# lt308x_test_board-v0001.net
KiCad netlist of a schematic drawn in EAGLE
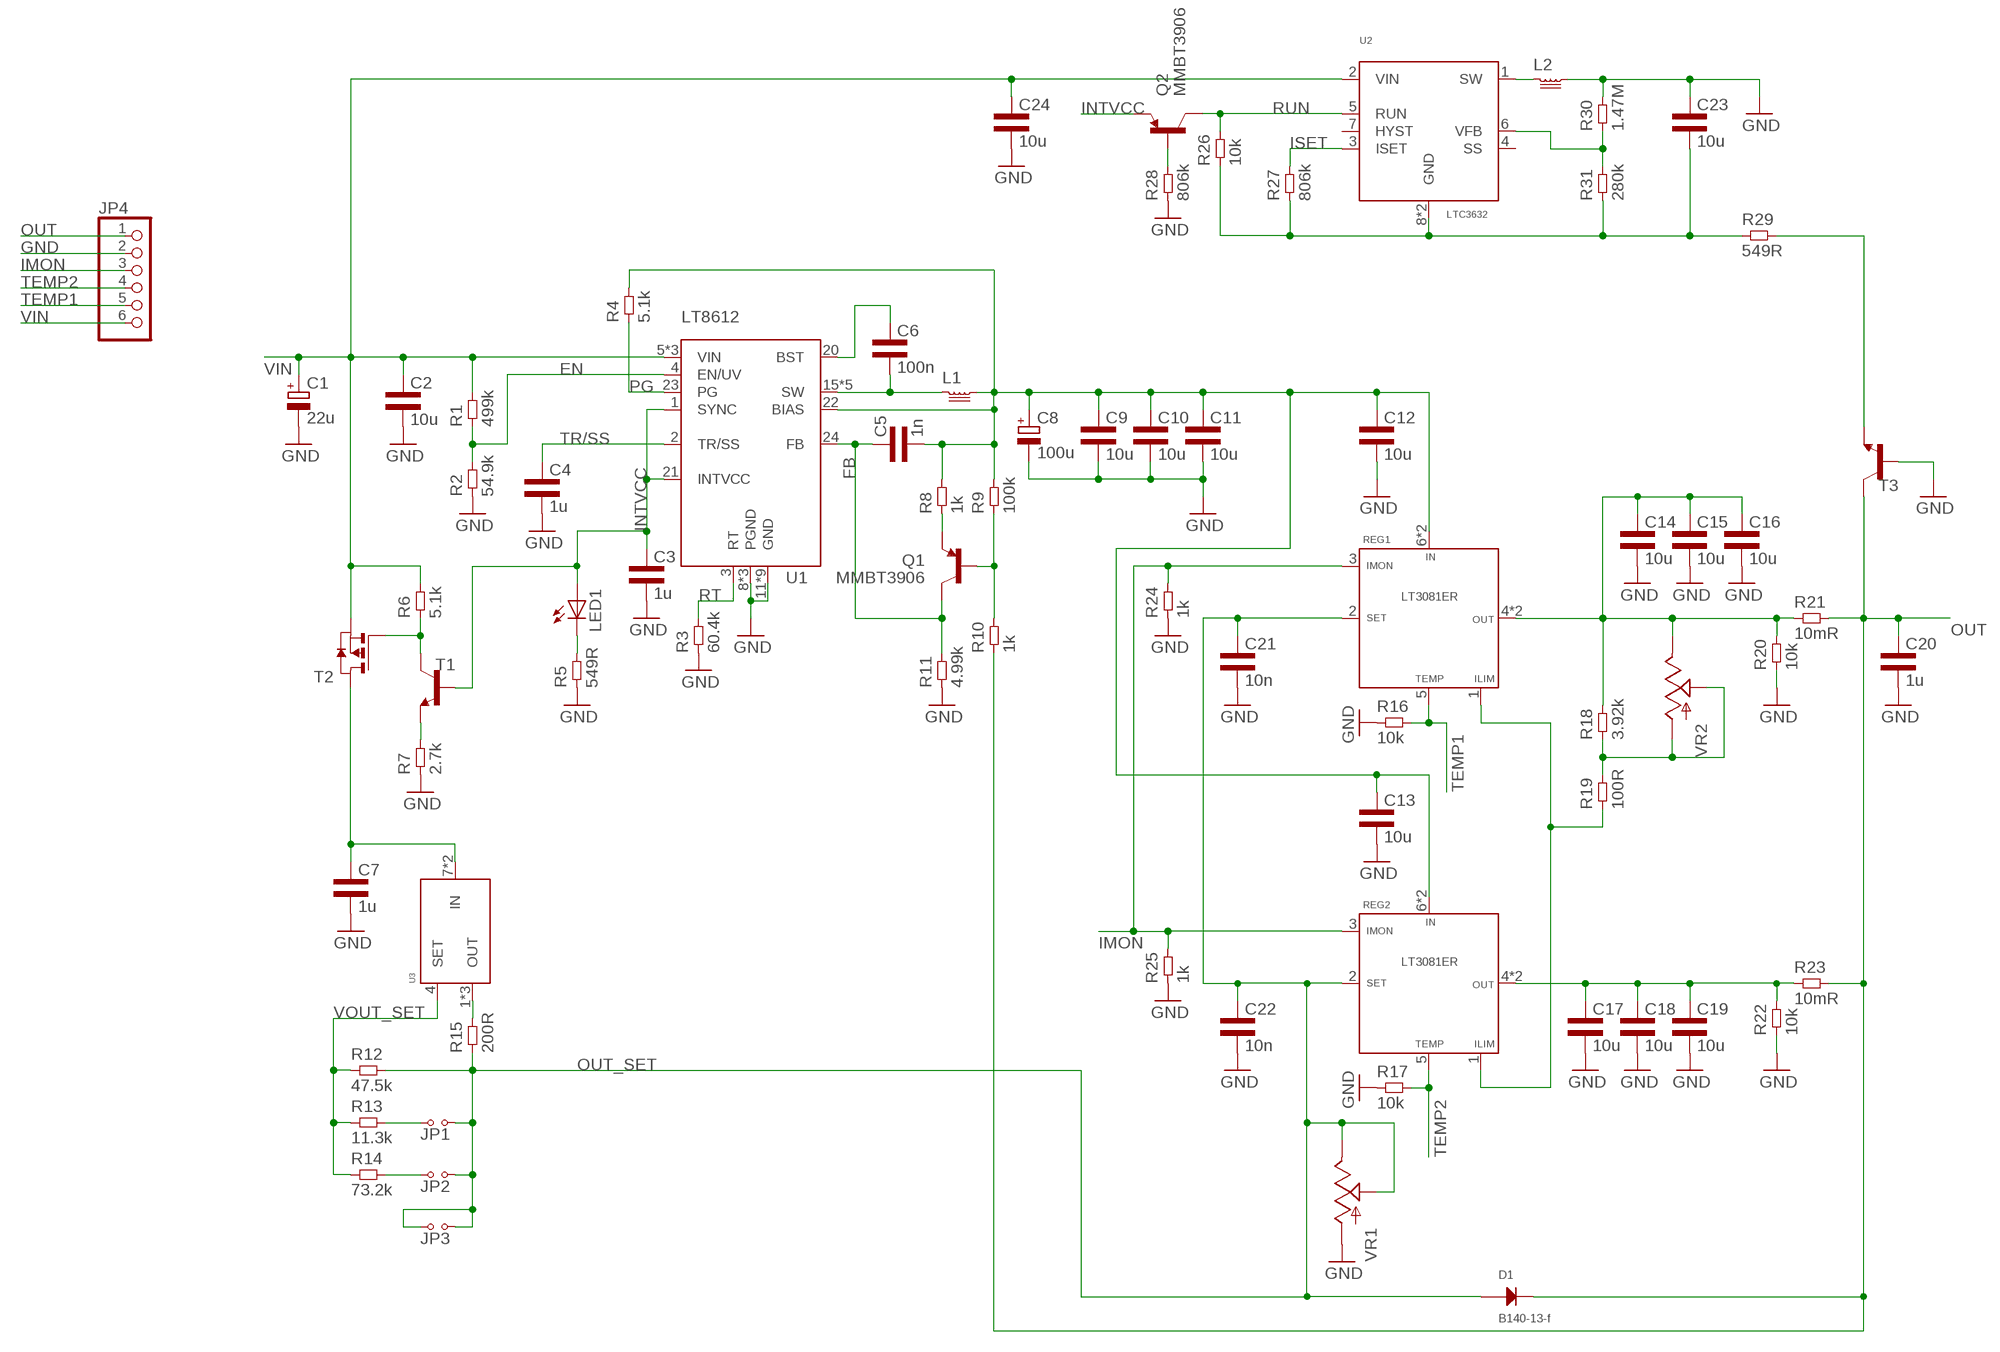
[diagram p0: schematic, sheet 1]

(export (version "E")
  (design (tool "Eeschema 10.0.6"))
  (components
    (comp (ref "C1")
      (value "22u")
      (footprint "eagle-import:UD-6,3X7,7_NICHICON")
      (libsource (lib "eagle-import") (part "CPOL-EUUD-6,3X7,7"))
    )
    (comp (ref "C2")
      (value "10u")
      (footprint "eagle-import:1210L3")
      (libsource (lib "eagle-import") (part "CAP1210L3"))
    )
    (comp (ref "C3")
      (value "1u")
      (footprint "eagle-import:0603L3")
      (libsource (lib "eagle-import") (part "CAP0603L3"))
    )
    (comp (ref "C4")
      (value "1u")
      (footprint "eagle-import:0603L3")
      (libsource (lib "eagle-import") (part "CAP0603L3"))
    )
    (comp (ref "C5")
      (value "1n")
      (footprint "eagle-import:0603L3")
      (libsource (lib "eagle-import") (part "CAP0603L3"))
    )
    (comp (ref "C6")
      (value "100n")
      (footprint "eagle-import:0603L3")
      (libsource (lib "eagle-import") (part "CAP0603L3"))
    )
    (comp (ref "C7")
      (value "1u")
      (footprint "eagle-import:0805L3")
      (libsource (lib "eagle-import") (part "CAP0805L3"))
    )
    (comp (ref "C8")
      (value "100u")
      (footprint "eagle-import:UD-6,3X7,7_NICHICON")
      (libsource (lib "eagle-import") (part "CPOL-EUUD-6,3X7,7"))
    )
    (comp (ref "C9")
      (value "10u")
      (footprint "eagle-import:1210L3")
      (libsource (lib "eagle-import") (part "CAP1210L3"))
    )
    (comp (ref "C10")
      (value "10u")
      (footprint "eagle-import:1210L3")
      (libsource (lib "eagle-import") (part "CAP1210L3"))
    )
    (comp (ref "C11")
      (value "10u")
      (footprint "eagle-import:1210L3")
      (libsource (lib "eagle-import") (part "CAP1210L3"))
    )
    (comp (ref "C12")
      (value "10u")
      (footprint "eagle-import:1210L3")
      (libsource (lib "eagle-import") (part "CAP1210L3"))
    )
    (comp (ref "C13")
      (value "10u")
      (footprint "eagle-import:1210L3")
      (libsource (lib "eagle-import") (part "CAP1210L3"))
    )
    (comp (ref "C14")
      (value "10u")
      (footprint "eagle-import:1210L3")
      (libsource (lib "eagle-import") (part "CAP1210L3"))
    )
    (comp (ref "C15")
      (value "10u")
      (footprint "eagle-import:1210L3")
      (libsource (lib "eagle-import") (part "CAP1210L3"))
    )
    (comp (ref "C16")
      (value "10u")
      (footprint "eagle-import:1210L3")
      (libsource (lib "eagle-import") (part "CAP1210L3"))
    )
    (comp (ref "C17")
      (value "10u")
      (footprint "eagle-import:1210L3")
      (libsource (lib "eagle-import") (part "CAP1210L3"))
    )
    (comp (ref "C18")
      (value "10u")
      (footprint "eagle-import:1210L3")
      (libsource (lib "eagle-import") (part "CAP1210L3"))
    )
    (comp (ref "C19")
      (value "10u")
      (footprint "eagle-import:1210L3")
      (libsource (lib "eagle-import") (part "CAP1210L3"))
    )
    (comp (ref "C20")
      (value "1u")
      (footprint "eagle-import:1206L3")
      (libsource (lib "eagle-import") (part "CAP1206L3"))
    )
    (comp (ref "C21")
      (value "10n")
      (footprint "eagle-import:0603L3")
      (libsource (lib "eagle-import") (part "CAP0603L3"))
    )
    (comp (ref "C22")
      (value "10n")
      (footprint "eagle-import:0603L3")
      (libsource (lib "eagle-import") (part "CAP0603L3"))
    )
    (comp (ref "C23")
      (value "10u")
      (footprint "eagle-import:0805L3")
      (libsource (lib "eagle-import") (part "CAP0805L3"))
    )
    (comp (ref "C24")
      (value "10u")
      (footprint "eagle-import:0805L3")
      (libsource (lib "eagle-import") (part "CAP0805L3"))
    )
    (comp (ref "D1")
      (value "B140-13-f")
      (footprint "eagle-import:SMA-2")
      (libsource (lib "eagle-import") (part "DIODESMA"))
    )
    (comp (ref "JP1")
      (value "JUMPER2")
      (footprint "eagle-import:JUMPER2")
      (libsource (lib "eagle-import") (part "JUMPER2"))
    )
    (comp (ref "JP2")
      (value "JUMPER2")
      (footprint "eagle-import:JUMPER2")
      (libsource (lib "eagle-import") (part "JUMPER2"))
    )
    (comp (ref "JP3")
      (value "JUMPER2")
      (footprint "eagle-import:JUMPER2")
      (libsource (lib "eagle-import") (part "JUMPER2"))
    )
    (comp (ref "JP4")
      (value "PINHD-1X6")
      (footprint "eagle-import:1X06")
      (libsource (lib "eagle-import") (part "PINHD-1X6"))
    )
    (comp (ref "L1")
      (value "INDUCTOR10.5X10.5")
      (footprint "eagle-import:10.5X10.5")
      (libsource (lib "eagle-import") (part "INDUCTOR10.5X10.5"))
    )
    (comp (ref "L2")
      (value "INDUCTOR1210L1")
      (footprint "eagle-import:1210L1")
      (libsource (lib "eagle-import") (part "INDUCTOR1210L1"))
    )
    (comp (ref "LED1")
      (value "LEDCHIPLED_0805")
      (footprint "eagle-import:CHIPLED_0805")
      (libsource (lib "eagle-import") (part "LEDCHIPLED_0805"))
    )
    (comp (ref "Q1")
      (value "MMBT3906")
      (footprint "eagle-import:SOT23")
      (libsource (lib "eagle-import") (part "TRANSISTOR_PNPMMBT3906"))
    )
    (comp (ref "Q2")
      (value "MMBT3906")
      (footprint "eagle-import:SOT23")
      (libsource (lib "eagle-import") (part "TRANSISTOR_PNPMMBT3906"))
    )
    (comp (ref "R1")
      (value "499k")
      (footprint "eagle-import:0603L3")
      (libsource (lib "eagle-import") (part "RES0603L3"))
    )
    (comp (ref "R2")
      (value "54.9k")
      (footprint "eagle-import:0603L3")
      (libsource (lib "eagle-import") (part "RES0603L3"))
    )
    (comp (ref "R3")
      (value "60.4k")
      (footprint "eagle-import:0603L3")
      (libsource (lib "eagle-import") (part "RES0603L3"))
    )
    (comp (ref "R4")
      (value "5.1k")
      (footprint "eagle-import:0603L3")
      (libsource (lib "eagle-import") (part "RES0603L3"))
    )
    (comp (ref "R5")
      (value "549R")
      (footprint "eagle-import:0603L3")
      (libsource (lib "eagle-import") (part "RES0603L3"))
    )
    (comp (ref "R6")
      (value "5.1k")
      (footprint "eagle-import:0603L3")
      (libsource (lib "eagle-import") (part "RES0603L3"))
    )
    (comp (ref "R7")
      (value "2.7k")
      (footprint "eagle-import:0603L3")
      (libsource (lib "eagle-import") (part "RES0603L3"))
    )
    (comp (ref "R8")
      (value "1k")
      (footprint "eagle-import:0603L3")
      (libsource (lib "eagle-import") (part "RES0603L3"))
    )
    (comp (ref "R9")
      (value "100k")
      (footprint "eagle-import:0603L3")
      (libsource (lib "eagle-import") (part "RES0603L3"))
    )
    (comp (ref "R10")
      (value "1k")
      (footprint "eagle-import:0603L3")
      (libsource (lib "eagle-import") (part "RES0603L3"))
    )
    (comp (ref "R11")
      (value "4.99k")
      (footprint "eagle-import:0603L3")
      (libsource (lib "eagle-import") (part "RES0603L3"))
    )
    (comp (ref "R12")
      (value "47.5k")
      (footprint "eagle-import:0603L3")
      (libsource (lib "eagle-import") (part "RES0603L3"))
    )
    (comp (ref "R13")
      (value "11.3k")
      (footprint "eagle-import:0603L3")
      (libsource (lib "eagle-import") (part "RES0603L3"))
    )
    (comp (ref "R14")
      (value "73.2k")
      (footprint "eagle-import:0603L3")
      (libsource (lib "eagle-import") (part "RES0603L3"))
    )
    (comp (ref "R15")
      (value "200R")
      (footprint "eagle-import:0805L3")
      (libsource (lib "eagle-import") (part "RES0805L3"))
    )
    (comp (ref "R16")
      (value "10k")
      (footprint "eagle-import:0603L3")
      (libsource (lib "eagle-import") (part "RES0603L3"))
    )
    (comp (ref "R17")
      (value "10k")
      (footprint "eagle-import:0603L3")
      (libsource (lib "eagle-import") (part "RES0603L3"))
    )
    (comp (ref "R18")
      (value "3.92k")
      (footprint "eagle-import:0603L3")
      (libsource (lib "eagle-import") (part "RES0603L3"))
    )
    (comp (ref "R19")
      (value "100R")
      (footprint "eagle-import:0603L3")
      (libsource (lib "eagle-import") (part "RES0603L3"))
    )
    (comp (ref "R20")
      (value "10k")
      (footprint "eagle-import:1210L3")
      (libsource (lib "eagle-import") (part "RES1210L3"))
    )
    (comp (ref "R21")
      (value "10mR")
      (footprint "eagle-import:1210L3")
      (libsource (lib "eagle-import") (part "RES1210L3"))
    )
    (comp (ref "R22")
      (value "10k")
      (footprint "eagle-import:1210L3")
      (libsource (lib "eagle-import") (part "RES1210L3"))
    )
    (comp (ref "R23")
      (value "10mR")
      (footprint "eagle-import:1210L3")
      (libsource (lib "eagle-import") (part "RES1210L3"))
    )
    (comp (ref "R24")
      (value "1k")
      (footprint "eagle-import:0603L3")
      (libsource (lib "eagle-import") (part "RES0603L3"))
    )
    (comp (ref "R25")
      (value "1k")
      (footprint "eagle-import:0603L3")
      (libsource (lib "eagle-import") (part "RES0603L3"))
    )
    (comp (ref "R26")
      (value "10k")
      (footprint "eagle-import:0603L3")
      (libsource (lib "eagle-import") (part "RES0603L3"))
    )
    (comp (ref "R27")
      (value "806k")
      (footprint "eagle-import:0603L3")
      (libsource (lib "eagle-import") (part "RES0603L3"))
    )
    (comp (ref "R28")
      (value "806k")
      (footprint "eagle-import:0603L3")
      (libsource (lib "eagle-import") (part "RES0603L3"))
    )
    (comp (ref "R29")
      (value "549R")
      (footprint "eagle-import:0603L3")
      (libsource (lib "eagle-import") (part "RES0603L3"))
    )
    (comp (ref "R30")
      (value "1.47M")
      (footprint "eagle-import:0603L3")
      (libsource (lib "eagle-import") (part "RES0603L3"))
    )
    (comp (ref "R31")
      (value "280k")
      (footprint "eagle-import:0603L3")
      (libsource (lib "eagle-import") (part "RES0603L3"))
    )
    (comp (ref "REG1")
      (value "LT3081ER")
      (footprint "eagle-import:DPAK-7")
      (libsource (lib "eagle-import") (part "LT3081ER"))
    )
    (comp (ref "REG2")
      (value "LT3081ER")
      (footprint "eagle-import:DPAK-7")
      (libsource (lib "eagle-import") (part "LT3081ER"))
    )
    (comp (ref "T1")
      (value "TRANSISTOR_MMBT3904LT1-NPN-SOT23-BEC")
      (footprint "eagle-import:TRANSISTOR_SOT23-BEC")
      (libsource (lib "eagle-import") (part "TRANSISTOR_-NPN-SOT23-BECMMBT3904LT1"))
    )
    (comp (ref "T2")
      (value "PMOSSOT23")
      (footprint "eagle-import:SOT-23")
      (libsource (lib "eagle-import") (part "PMOSSOT23"))
    )
    (comp (ref "T3")
      (value "TRANSISTOR_MMBT3904LT1-NPN-SOT23-BEC")
      (footprint "eagle-import:TRANSISTOR_SOT23-BEC")
      (libsource (lib "eagle-import") (part "TRANSISTOR_-NPN-SOT23-BECMMBT3904LT1"))
    )
    (comp (ref "U1")
      (value "LT8612")
      (footprint "eagle-import:UDE-3X6")
      (libsource (lib "eagle-import") (part "LT8612"))
    )
    (comp (ref "U2")
      (value "LTC3632")
      (footprint "eagle-import:DFN-3X3")
      (libsource (lib "eagle-import") (part "LTC3632"))
    )
    (comp (ref "U3")
      (value "LT3092")
      (footprint "eagle-import:DD-8")
      (libsource (lib "eagle-import") (part "LT3092"))
    )
    (comp (ref "VR1")
      (value "POT")
      (footprint "eagle-import:ALPS_POT")
      (libsource (lib "eagle-import") (part "POT"))
    )
    (comp (ref "VR2")
      (value "POT")
      (footprint "eagle-import:ALPS_POT")
      (libsource (lib "eagle-import") (part "POT"))
    )
  )
  (nets
    (net (code "1") (name "/EN") (class "Default")
      (node (ref "R1") (pin "P$1") (pinfunction "1_P$1") (pintype "bidirectional"))
      (node (ref "R2") (pin "P$2") (pinfunction "2_P$2") (pintype "bidirectional"))
      (node (ref "U1") (pin "4") (pinfunction "EN/UV_4") (pintype "bidirectional"))
    )
    (net (code "2") (name "/FB") (class "Default")
      (node (ref "C5") (pin "P$1") (pinfunction "1_P$1") (pintype "bidirectional"))
      (node (ref "Q1") (pin "3") (pinfunction "C_3") (pintype "passive"))
      (node (ref "R11") (pin "P$2") (pinfunction "2_P$2") (pintype "bidirectional"))
      (node (ref "U1") (pin "24") (pinfunction "FB_24") (pintype "bidirectional"))
    )
    (net (code "3") (name "/IMON") (class "Default")
      (node (ref "JP4") (pin "3") (pinfunction "3_3") (pintype "passive"))
      (node (ref "R24") (pin "P$2") (pinfunction "2_P$2") (pintype "bidirectional"))
      (node (ref "R25") (pin "P$2") (pinfunction "2_P$2") (pintype "bidirectional"))
      (node (ref "REG1") (pin "3") (pinfunction "IMON_3") (pintype "bidirectional"))
      (node (ref "REG2") (pin "3") (pinfunction "IMON_3") (pintype "bidirectional"))
    )
    (net (code "4") (name "/INTVCC") (class "Default")
      (node (ref "C3") (pin "P$1") (pinfunction "1_P$1") (pintype "bidirectional"))
      (node (ref "LED1") (pin "A") (pinfunction "A_A") (pintype "passive"))
      (node (ref "Q2") (pin "2") (pinfunction "E_2") (pintype "passive"))
      (node (ref "T1") (pin "B") (pinfunction "B_B") (pintype "passive"))
      (node (ref "U1") (pin "1") (pinfunction "SYNC_1") (pintype "bidirectional"))
      (node (ref "U1") (pin "21") (pinfunction "INTVCC_21") (pintype "bidirectional"))
    )
    (net (code "5") (name "/ISET") (class "Default")
      (node (ref "R27") (pin "P$2") (pinfunction "2_P$2") (pintype "bidirectional"))
      (node (ref "U2") (pin "3") (pinfunction "ISET_3") (pintype "bidirectional"))
    )
    (net (code "6") (name "/OUT") (class "Default")
      (node (ref "C20") (pin "1") (pinfunction "1_1") (pintype "bidirectional"))
      (node (ref "D1") (pin "2") (pinfunction "CATHODE_2") (pintype "bidirectional"))
      (node (ref "JP4") (pin "1") (pinfunction "1_1") (pintype "passive"))
      (node (ref "R10") (pin "P$1") (pinfunction "1_P$1") (pintype "bidirectional"))
      (node (ref "R21") (pin "P$2") (pinfunction "2_P$2") (pintype "bidirectional"))
      (node (ref "R23") (pin "P$2") (pinfunction "2_P$2") (pintype "bidirectional"))
      (node (ref "T3") (pin "C") (pinfunction "C_C") (pintype "passive"))
    )
    (net (code "7") (name "/OUT_SET") (class "Default")
      (node (ref "C21") (pin "P$1") (pinfunction "1_P$1") (pintype "bidirectional"))
      (node (ref "C22") (pin "P$1") (pinfunction "1_P$1") (pintype "bidirectional"))
      (node (ref "D1") (pin "1") (pinfunction "ANODE_1") (pintype "bidirectional"))
      (node (ref "JP1") (pin "2") (pinfunction "2_2") (pintype "bidirectional"))
      (node (ref "JP2") (pin "2") (pinfunction "2_2") (pintype "bidirectional"))
      (node (ref "JP3") (pin "1") (pinfunction "1_1") (pintype "bidirectional"))
      (node (ref "JP3") (pin "2") (pinfunction "2_2") (pintype "bidirectional"))
      (node (ref "R12") (pin "P$2") (pinfunction "2_P$2") (pintype "bidirectional"))
      (node (ref "R15") (pin "1") (pinfunction "1_1") (pintype "bidirectional"))
      (node (ref "REG1") (pin "2") (pinfunction "SET_2") (pintype "bidirectional"))
      (node (ref "REG2") (pin "2") (pinfunction "SET_2") (pintype "bidirectional"))
      (node (ref "VR1") (pin "P$1") (pinfunction "E_P$1") (pintype "passive"))
      (node (ref "VR1") (pin "P$2") (pinfunction "S_P$2") (pintype "passive"))
    )
    (net (code "8") (name "/PG") (class "Default")
      (node (ref "R4") (pin "P$1") (pinfunction "1_P$1") (pintype "bidirectional"))
      (node (ref "U1") (pin "23") (pinfunction "PG_23") (pintype "bidirectional"))
    )
    (net (code "9") (name "/RT") (class "Default")
      (node (ref "R3") (pin "P$2") (pinfunction "2_P$2") (pintype "bidirectional"))
      (node (ref "U1") (pin "3") (pinfunction "RT_3") (pintype "bidirectional"))
    )
    (net (code "10") (name "/RUN") (class "Default")
      (node (ref "Q2") (pin "3") (pinfunction "C_3") (pintype "passive"))
      (node (ref "R26") (pin "P$2") (pinfunction "2_P$2") (pintype "bidirectional"))
      (node (ref "U2") (pin "5") (pinfunction "RUN_5") (pintype "bidirectional"))
    )
    (net (code "11") (name "/TEMP1") (class "Default")
      (node (ref "JP4") (pin "5") (pinfunction "5_5") (pintype "passive"))
      (node (ref "R16") (pin "P$2") (pinfunction "2_P$2") (pintype "bidirectional"))
      (node (ref "REG1") (pin "5") (pinfunction "TEMP_5") (pintype "bidirectional"))
    )
    (net (code "12") (name "/TEMP2") (class "Default")
      (node (ref "JP4") (pin "4") (pinfunction "4_4") (pintype "passive"))
      (node (ref "R17") (pin "P$2") (pinfunction "2_P$2") (pintype "bidirectional"))
      (node (ref "REG2") (pin "5") (pinfunction "TEMP_5") (pintype "bidirectional"))
    )
    (net (code "13") (name "/TR{slash}SS") (class "Default")
      (node (ref "C4") (pin "P$1") (pinfunction "1_P$1") (pintype "bidirectional"))
      (node (ref "U1") (pin "2") (pinfunction "TR/SS_2") (pintype "bidirectional"))
    )
    (net (code "14") (name "/VIN") (class "Default")
      (node (ref "C1") (pin "+") (pinfunction "+_+") (pintype "passive"))
      (node (ref "C2") (pin "P$1") (pinfunction "1_P$1") (pintype "bidirectional"))
      (node (ref "C24") (pin "1") (pinfunction "1_1") (pintype "bidirectional"))
      (node (ref "JP4") (pin "6") (pinfunction "6_6") (pintype "passive"))
      (node (ref "R1") (pin "P$2") (pinfunction "2_P$2") (pintype "bidirectional"))
      (node (ref "R6") (pin "P$2") (pinfunction "2_P$2") (pintype "bidirectional"))
      (node (ref "T2") (pin "2") (pinfunction "S_2") (pintype "passive"))
      (node (ref "U1") (pin "5") (pinfunction "VIN_5") (pintype "bidirectional"))
      (node (ref "U1") (pin "6") (pinfunction "VIN_6") (pintype "bidirectional"))
      (node (ref "U1") (pin "7") (pinfunction "VIN_7") (pintype "bidirectional"))
      (node (ref "U2") (pin "2") (pinfunction "VIN_2") (pintype "bidirectional"))
    )
    (net (code "15") (name "/VOUT_SET") (class "Default")
      (node (ref "R12") (pin "P$1") (pinfunction "1_P$1") (pintype "bidirectional"))
      (node (ref "R13") (pin "P$1") (pinfunction "1_P$1") (pintype "bidirectional"))
      (node (ref "R14") (pin "P$1") (pinfunction "1_P$1") (pintype "bidirectional"))
      (node (ref "U3") (pin "4") (pinfunction "SET_4") (pintype "bidirectional"))
    )
    (net (code "16") (name "GND") (class "Default")
      (node (ref "C1") (pin "-") (pinfunction "-_-") (pintype "passive"))
      (node (ref "C10") (pin "P$2") (pinfunction "2_P$2") (pintype "bidirectional"))
      (node (ref "C11") (pin "P$2") (pinfunction "2_P$2") (pintype "bidirectional"))
      (node (ref "C12") (pin "P$2") (pinfunction "2_P$2") (pintype "bidirectional"))
      (node (ref "C13") (pin "P$2") (pinfunction "2_P$2") (pintype "bidirectional"))
      (node (ref "C14") (pin "P$2") (pinfunction "2_P$2") (pintype "bidirectional"))
      (node (ref "C15") (pin "P$2") (pinfunction "2_P$2") (pintype "bidirectional"))
      (node (ref "C16") (pin "P$2") (pinfunction "2_P$2") (pintype "bidirectional"))
      (node (ref "C17") (pin "P$2") (pinfunction "2_P$2") (pintype "bidirectional"))
      (node (ref "C18") (pin "P$2") (pinfunction "2_P$2") (pintype "bidirectional"))
      (node (ref "C19") (pin "P$2") (pinfunction "2_P$2") (pintype "bidirectional"))
      (node (ref "C2") (pin "P$2") (pinfunction "2_P$2") (pintype "bidirectional"))
      (node (ref "C20") (pin "2") (pinfunction "2_2") (pintype "bidirectional"))
      (node (ref "C21") (pin "P$2") (pinfunction "2_P$2") (pintype "bidirectional"))
      (node (ref "C22") (pin "P$2") (pinfunction "2_P$2") (pintype "bidirectional"))
      (node (ref "C23") (pin "1") (pinfunction "1_1") (pintype "bidirectional"))
      (node (ref "C24") (pin "2") (pinfunction "2_2") (pintype "bidirectional"))
      (node (ref "C3") (pin "P$2") (pinfunction "2_P$2") (pintype "bidirectional"))
      (node (ref "C4") (pin "P$2") (pinfunction "2_P$2") (pintype "bidirectional"))
      (node (ref "C7") (pin "2") (pinfunction "2_2") (pintype "bidirectional"))
      (node (ref "C8") (pin "-") (pinfunction "-_-") (pintype "passive"))
      (node (ref "C9") (pin "P$2") (pinfunction "2_P$2") (pintype "bidirectional"))
      (node (ref "JP4") (pin "2") (pinfunction "2_2") (pintype "passive"))
      (node (ref "L2") (pin "2") (pinfunction "2_2") (pintype "bidirectional"))
      (node (ref "R11") (pin "P$1") (pinfunction "1_P$1") (pintype "bidirectional"))
      (node (ref "R16") (pin "P$1") (pinfunction "1_P$1") (pintype "bidirectional"))
      (node (ref "R17") (pin "P$1") (pinfunction "1_P$1") (pintype "bidirectional"))
      (node (ref "R2") (pin "P$1") (pinfunction "1_P$1") (pintype "bidirectional"))
      (node (ref "R20") (pin "P$1") (pinfunction "1_P$1") (pintype "bidirectional"))
      (node (ref "R22") (pin "P$1") (pinfunction "1_P$1") (pintype "bidirectional"))
      (node (ref "R24") (pin "P$1") (pinfunction "1_P$1") (pintype "bidirectional"))
      (node (ref "R25") (pin "P$1") (pinfunction "1_P$1") (pintype "bidirectional"))
      (node (ref "R28") (pin "P$1") (pinfunction "1_P$1") (pintype "bidirectional"))
      (node (ref "R3") (pin "P$1") (pinfunction "1_P$1") (pintype "bidirectional"))
      (node (ref "R30") (pin "P$2") (pinfunction "2_P$2") (pintype "bidirectional"))
      (node (ref "R5") (pin "P$1") (pinfunction "1_P$1") (pintype "bidirectional"))
      (node (ref "R7") (pin "P$1") (pinfunction "1_P$1") (pintype "bidirectional"))
      (node (ref "T3") (pin "B") (pinfunction "B_B") (pintype "passive"))
      (node (ref "U1") (pin "10") (pinfunction "PGND_10") (pintype "bidirectional"))
      (node (ref "U1") (pin "11") (pinfunction "GND_11") (pintype "bidirectional"))
      (node (ref "U1") (pin "12") (pinfunction "GND_12") (pintype "bidirectional"))
      (node (ref "U1") (pin "13") (pinfunction "GND_13") (pintype "bidirectional"))
      (node (ref "U1") (pin "14") (pinfunction "GND_14") (pintype "bidirectional"))
      (node (ref "U1") (pin "25") (pinfunction "GND_25") (pintype "bidirectional"))
      (node (ref "U1") (pin "26") (pinfunction "GND_26") (pintype "bidirectional"))
      (node (ref "U1") (pin "27") (pinfunction "GND_27") (pintype "bidirectional"))
      (node (ref "U1") (pin "28") (pinfunction "GND_28") (pintype "bidirectional"))
      (node (ref "U1") (pin "8") (pinfunction "PGND_8") (pintype "bidirectional"))
      (node (ref "U1") (pin "9") (pinfunction "PGND_9") (pintype "bidirectional"))
      (node (ref "U1") (pin "TP") (pinfunction "GND_TP") (pintype "bidirectional"))
      (node (ref "VR1") (pin "P$3") (pinfunction "A_P$3") (pintype "passive"))
    )
    (net (code "17") (name "Net-(C6-1)") (class "Default")
      (node (ref "C6") (pin "P$1") (pinfunction "1_P$1") (pintype "bidirectional"))
      (node (ref "U1") (pin "20") (pinfunction "BST_20") (pintype "bidirectional"))
    )
    (net (code "18") (name "Net-(C6-2)") (class "Default")
      (node (ref "C6") (pin "P$2") (pinfunction "2_P$2") (pintype "bidirectional"))
      (node (ref "L1") (pin "1") (pinfunction "1_1") (pintype "bidirectional"))
      (node (ref "U1") (pin "15") (pinfunction "SW_15") (pintype "bidirectional"))
      (node (ref "U1") (pin "16") (pinfunction "SW_16") (pintype "bidirectional"))
      (node (ref "U1") (pin "17") (pinfunction "SW_17") (pintype "bidirectional"))
      (node (ref "U1") (pin "18") (pinfunction "SW_18") (pintype "bidirectional"))
      (node (ref "U1") (pin "19") (pinfunction "SW_19") (pintype "bidirectional"))
    )
    (net (code "19") (name "Net-(C10-1)") (class "Default")
      (node (ref "C10") (pin "P$1") (pinfunction "1_P$1") (pintype "bidirectional"))
      (node (ref "C11") (pin "P$1") (pinfunction "1_P$1") (pintype "bidirectional"))
      (node (ref "C12") (pin "P$1") (pinfunction "1_P$1") (pintype "bidirectional"))
      (node (ref "C13") (pin "P$1") (pinfunction "1_P$1") (pintype "bidirectional"))
      (node (ref "C5") (pin "P$2") (pinfunction "2_P$2") (pintype "bidirectional"))
      (node (ref "C8") (pin "+") (pinfunction "+_+") (pintype "passive"))
      (node (ref "C9") (pin "P$1") (pinfunction "1_P$1") (pintype "bidirectional"))
      (node (ref "L1") (pin "2") (pinfunction "2_2") (pintype "bidirectional"))
      (node (ref "R4") (pin "P$2") (pinfunction "2_P$2") (pintype "bidirectional"))
      (node (ref "R8") (pin "P$2") (pinfunction "2_P$2") (pintype "bidirectional"))
      (node (ref "R9") (pin "P$2") (pinfunction "2_P$2") (pintype "bidirectional"))
      (node (ref "REG1") (pin "6") (pinfunction "IN_6") (pintype "bidirectional"))
      (node (ref "REG1") (pin "7") (pinfunction "IN_7") (pintype "bidirectional"))
      (node (ref "REG2") (pin "6") (pinfunction "IN_6") (pintype "bidirectional"))
      (node (ref "REG2") (pin "7") (pinfunction "IN_7") (pintype "bidirectional"))
      (node (ref "U1") (pin "22") (pinfunction "BIAS_22") (pintype "bidirectional"))
    )
    (net (code "20") (name "Net-(C14-1)") (class "Default")
      (node (ref "C14") (pin "P$1") (pinfunction "1_P$1") (pintype "bidirectional"))
      (node (ref "C15") (pin "P$1") (pinfunction "1_P$1") (pintype "bidirectional"))
      (node (ref "C16") (pin "P$1") (pinfunction "1_P$1") (pintype "bidirectional"))
      (node (ref "R18") (pin "P$2") (pinfunction "2_P$2") (pintype "bidirectional"))
      (node (ref "R20") (pin "P$2") (pinfunction "2_P$2") (pintype "bidirectional"))
      (node (ref "R21") (pin "P$1") (pinfunction "1_P$1") (pintype "bidirectional"))
      (node (ref "REG1") (pin "4") (pinfunction "OUT_4") (pintype "bidirectional"))
      (node (ref "REG1") (pin "TAB") (pinfunction "OUT_TAB") (pintype "bidirectional"))
      (node (ref "VR2") (pin "P$1") (pinfunction "E_P$1") (pintype "passive"))
    )
    (net (code "21") (name "Net-(C17-1)") (class "Default")
      (node (ref "C17") (pin "P$1") (pinfunction "1_P$1") (pintype "bidirectional"))
      (node (ref "C18") (pin "P$1") (pinfunction "1_P$1") (pintype "bidirectional"))
      (node (ref "C19") (pin "P$1") (pinfunction "1_P$1") (pintype "bidirectional"))
      (node (ref "R22") (pin "P$2") (pinfunction "2_P$2") (pintype "bidirectional"))
      (node (ref "R23") (pin "P$1") (pinfunction "1_P$1") (pintype "bidirectional"))
      (node (ref "REG2") (pin "4") (pinfunction "OUT_4") (pintype "bidirectional"))
      (node (ref "REG2") (pin "TAB") (pinfunction "OUT_TAB") (pintype "bidirectional"))
    )
    (net (code "22") (name "Net-(Q1-B)") (class "Default")
      (node (ref "Q1") (pin "1") (pinfunction "B_1") (pintype "passive"))
      (node (ref "R10") (pin "P$2") (pinfunction "2_P$2") (pintype "bidirectional"))
      (node (ref "R9") (pin "P$1") (pinfunction "1_P$1") (pintype "bidirectional"))
    )
    (net (code "23") (name "Net-(Q1-E)") (class "Default")
      (node (ref "Q1") (pin "2") (pinfunction "E_2") (pintype "passive"))
      (node (ref "R8") (pin "P$1") (pinfunction "1_P$1") (pintype "bidirectional"))
    )
    (net (code "24") (name "Net-(Q2-B)") (class "Default")
      (node (ref "Q2") (pin "1") (pinfunction "B_1") (pintype "passive"))
      (node (ref "R28") (pin "P$2") (pinfunction "2_P$2") (pintype "bidirectional"))
    )
    (net (code "25") (name "Net-(R5-2)") (class "Default")
      (node (ref "LED1") (pin "C") (pinfunction "C_C") (pintype "passive"))
      (node (ref "R5") (pin "P$2") (pinfunction "2_P$2") (pintype "bidirectional"))
    )
    (net (code "26") (name "Net-(R6-1)") (class "Default")
      (node (ref "R6") (pin "P$1") (pinfunction "1_P$1") (pintype "bidirectional"))
      (node (ref "T1") (pin "C") (pinfunction "C_C") (pintype "passive"))
      (node (ref "T2") (pin "3") (pinfunction "G_3") (pintype "passive"))
    )
    (net (code "27") (name "Net-(R7-2)") (class "Default")
      (node (ref "R7") (pin "P$2") (pinfunction "2_P$2") (pintype "bidirectional"))
      (node (ref "T1") (pin "E") (pinfunction "E_E") (pintype "passive"))
    )
    (net (code "28") (name "Net-(R13-2)") (class "Default")
      (node (ref "JP1") (pin "1") (pinfunction "1_1") (pintype "bidirectional"))
      (node (ref "R13") (pin "P$2") (pinfunction "2_P$2") (pintype "bidirectional"))
    )
    (net (code "29") (name "Net-(R14-2)") (class "Default")
      (node (ref "JP2") (pin "1") (pinfunction "1_1") (pintype "bidirectional"))
      (node (ref "R14") (pin "P$2") (pinfunction "2_P$2") (pintype "bidirectional"))
    )
    (net (code "30") (name "Net-(R15-Pad2)") (class "Default")
      (node (ref "R15") (pin "2") (pinfunction "2_2") (pintype "bidirectional"))
      (node (ref "U3") (pin "1") (pinfunction "OUT_1") (pintype "bidirectional"))
      (node (ref "U3") (pin "2") (pinfunction "OUT_2") (pintype "bidirectional"))
      (node (ref "U3") (pin "9") (pinfunction "OUT_9") (pintype "bidirectional"))
    )
    (net (code "31") (name "Net-(R18-1)") (class "Default")
      (node (ref "R18") (pin "P$1") (pinfunction "1_P$1") (pintype "bidirectional"))
      (node (ref "R19") (pin "P$2") (pinfunction "2_P$2") (pintype "bidirectional"))
      (node (ref "VR2") (pin "P$2") (pinfunction "S_P$2") (pintype "passive"))
      (node (ref "VR2") (pin "P$3") (pinfunction "A_P$3") (pintype "passive"))
    )
    (net (code "32") (name "Net-(R19-1)") (class "Default")
      (node (ref "R19") (pin "P$1") (pinfunction "1_P$1") (pintype "bidirectional"))
      (node (ref "REG1") (pin "1") (pinfunction "ILIM_1") (pintype "bidirectional"))
      (node (ref "REG2") (pin "1") (pinfunction "ILIM_1") (pintype "bidirectional"))
    )
    (net (code "33") (name "Net-(R26-1)") (class "Default")
      (node (ref "C23") (pin "2") (pinfunction "2_2") (pintype "bidirectional"))
      (node (ref "R26") (pin "P$1") (pinfunction "1_P$1") (pintype "bidirectional"))
      (node (ref "R27") (pin "P$1") (pinfunction "1_P$1") (pintype "bidirectional"))
      (node (ref "R29") (pin "P$1") (pinfunction "1_P$1") (pintype "bidirectional"))
      (node (ref "R31") (pin "P$1") (pinfunction "1_P$1") (pintype "bidirectional"))
      (node (ref "U2") (pin "8") (pinfunction "GND_8") (pintype "bidirectional"))
      (node (ref "U2") (pin "TP") (pinfunction "GND_TP") (pintype "bidirectional"))
    )
    (net (code "34") (name "Net-(R29-2)") (class "Default")
      (node (ref "R29") (pin "P$2") (pinfunction "2_P$2") (pintype "bidirectional"))
      (node (ref "T3") (pin "E") (pinfunction "E_E") (pintype "passive"))
    )
    (net (code "35") (name "Net-(R30-1)") (class "Default")
      (node (ref "R30") (pin "P$1") (pinfunction "1_P$1") (pintype "bidirectional"))
      (node (ref "R31") (pin "P$2") (pinfunction "2_P$2") (pintype "bidirectional"))
      (node (ref "U2") (pin "6") (pinfunction "VFB_6") (pintype "bidirectional"))
    )
    (net (code "36") (name "Net-(T2-D)") (class "Default")
      (node (ref "C7") (pin "1") (pinfunction "1_1") (pintype "bidirectional"))
      (node (ref "T2") (pin "1") (pinfunction "D_1") (pintype "passive"))
      (node (ref "U3") (pin "7") (pinfunction "IN_7") (pintype "bidirectional"))
      (node (ref "U3") (pin "8") (pinfunction "IN_8") (pintype "bidirectional"))
    )
    (net (code "37") (name "Net-(U2-SW)") (class "Default")
      (node (ref "L2") (pin "1") (pinfunction "1_1") (pintype "bidirectional"))
      (node (ref "U2") (pin "1") (pinfunction "SW_1") (pintype "bidirectional"))
    )
    (net (code "38") (name "unconnected-(U2-HYST-Pad7)") (class "Default")
      (node (ref "U2") (pin "7") (pinfunction "HYST_7") (pintype "bidirectional"))
    )
    (net (code "39") (name "unconnected-(U2-SS-Pad4)") (class "Default")
      (node (ref "U2") (pin "4") (pinfunction "SS_4") (pintype "bidirectional"))
    )
  )
)
